# Tariq.net
KiCad netlist of a schematic drawn in EAGLE
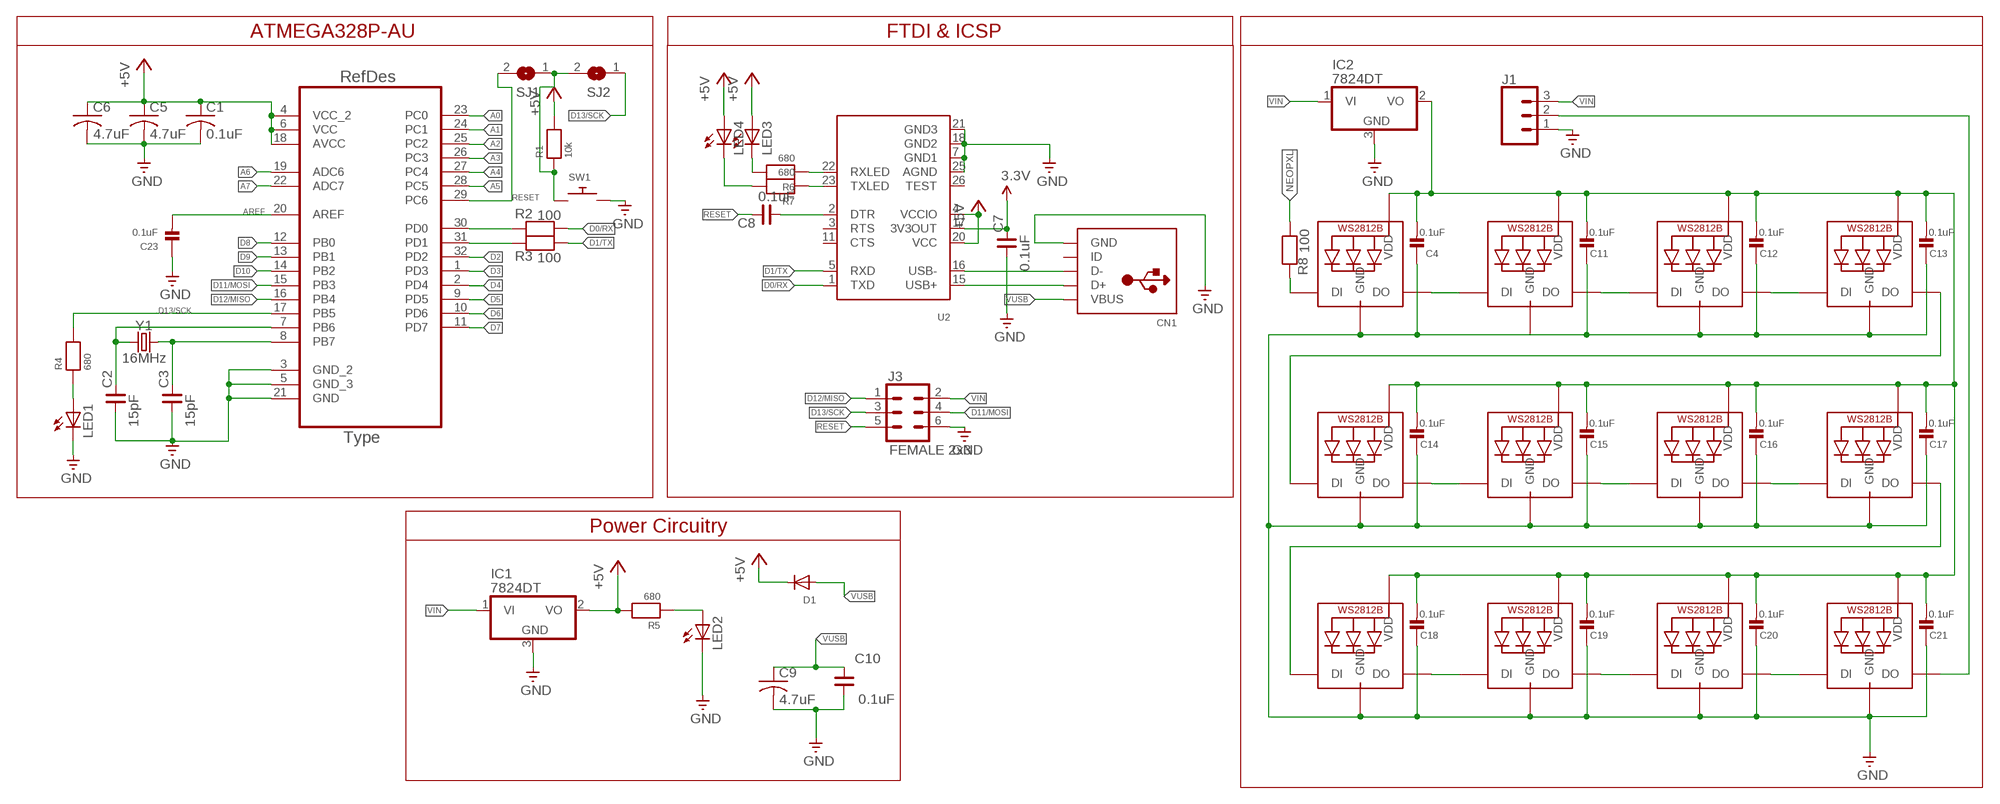
[diagram p0: schematic, sheet 1]

(export (version "E")
  (design (tool "Eeschema 10.0.6"))
  (components
    (comp (ref "C1")
      (value "0.1uF")
      (footprint "eagle-import:C0805")
      (libsource (lib "eagle-import") (part "C-USC0805"))
    )
    (comp (ref "C2")
      (value "15pF")
      (footprint "eagle-import:0805")
      (libsource (lib "eagle-import") (part "CNP-0805"))
    )
    (comp (ref "C3")
      (value "15pF")
      (footprint "eagle-import:0805")
      (libsource (lib "eagle-import") (part "CNP-0805"))
    )
    (comp (ref "C4")
      (value "0.1uF")
      (footprint "eagle-import:0603")
      (libsource (lib "eagle-import") (part "CAP_CERAMIC0603"))
    )
    (comp (ref "C5")
      (value "4.7uF")
      (footprint "eagle-import:C0805")
      (libsource (lib "eagle-import") (part "C-USC0805"))
    )
    (comp (ref "C6")
      (value "4.7uF")
      (footprint "eagle-import:C0805")
      (libsource (lib "eagle-import") (part "C-USC0805"))
    )
    (comp (ref "C7")
      (value "0.1uF")
      (footprint "eagle-import:0805")
      (libsource (lib "eagle-import") (part "CNP-0805"))
    )
    (comp (ref "C8")
      (value "0.1uF")
      (footprint "eagle-import:0805")
      (libsource (lib "eagle-import") (part "CNP-0805"))
    )
    (comp (ref "C9")
      (value "4.7uF")
      (footprint "eagle-import:C0805")
      (libsource (lib "eagle-import") (part "C-USC0805"))
    )
    (comp (ref "C10")
      (value "0.1uF")
      (footprint "eagle-import:0805")
      (libsource (lib "eagle-import") (part "CNP-0805"))
    )
    (comp (ref "C11")
      (value "0.1uF")
      (footprint "eagle-import:0603")
      (libsource (lib "eagle-import") (part "CAP_CERAMIC0603"))
    )
    (comp (ref "C12")
      (value "0.1uF")
      (footprint "eagle-import:0603")
      (libsource (lib "eagle-import") (part "CAP_CERAMIC0603"))
    )
    (comp (ref "C13")
      (value "0.1uF")
      (footprint "eagle-import:0603")
      (libsource (lib "eagle-import") (part "CAP_CERAMIC0603"))
    )
    (comp (ref "C14")
      (value "0.1uF")
      (footprint "eagle-import:0603")
      (libsource (lib "eagle-import") (part "CAP_CERAMIC0603"))
    )
    (comp (ref "C15")
      (value "0.1uF")
      (footprint "eagle-import:0603")
      (libsource (lib "eagle-import") (part "CAP_CERAMIC0603"))
    )
    (comp (ref "C16")
      (value "0.1uF")
      (footprint "eagle-import:0603")
      (libsource (lib "eagle-import") (part "CAP_CERAMIC0603"))
    )
    (comp (ref "C17")
      (value "0.1uF")
      (footprint "eagle-import:0603")
      (libsource (lib "eagle-import") (part "CAP_CERAMIC0603"))
    )
    (comp (ref "C18")
      (value "0.1uF")
      (footprint "eagle-import:0603")
      (libsource (lib "eagle-import") (part "CAP_CERAMIC0603"))
    )
    (comp (ref "C19")
      (value "0.1uF")
      (footprint "eagle-import:0603")
      (libsource (lib "eagle-import") (part "CAP_CERAMIC0603"))
    )
    (comp (ref "C20")
      (value "0.1uF")
      (footprint "eagle-import:0603")
      (libsource (lib "eagle-import") (part "CAP_CERAMIC0603"))
    )
    (comp (ref "C21")
      (value "0.1uF")
      (footprint "eagle-import:0603")
      (libsource (lib "eagle-import") (part "CAP_CERAMIC0603"))
    )
    (comp (ref "C23")
      (value "0.1uF")
      (footprint "eagle-import:0603")
      (libsource (lib "eagle-import") (part "CAP_CERAMIC0603"))
    )
    (comp (ref "CN1")
      (value "USBMINIB")
      (footprint "eagle-import:USB-MINIB")
      (libsource (lib "eagle-import") (part "USBMINIB"))
    )
    (comp (ref "D1")
      (value "DIODESOD-123")
      (footprint "eagle-import:SOD-123")
      (libsource (lib "eagle-import") (part "DIODESOD-123"))
    )
    (comp (ref "IC1")
      (value "7824DT")
      (footprint "eagle-import:TO252")
      (libsource (lib "eagle-import") (part "78DT24"))
    )
    (comp (ref "IC2")
      (value "7824DT")
      (footprint "eagle-import:TO252")
      (libsource (lib "eagle-import") (part "78DT24"))
    )
    (comp (ref "J1")
      (value "CONN_03")
      (footprint "eagle-import:1X03")
      (libsource (lib "eagle-import") (part "CONN_03"))
    )
    (comp (ref "J3")
      (value "FEMALE 2x3")
      (footprint "eagle-import:2X3")
      (libsource (lib "eagle-import") (part "CONN_03X2FEMALE"))
    )
    (comp (ref "LED1")
      (value "LEDCHIPLED_0805")
      (footprint "eagle-import:CHIPLED_0805")
      (libsource (lib "eagle-import") (part "LEDCHIPLED_0805"))
    )
    (comp (ref "LED2")
      (value "LEDCHIPLED_0805")
      (footprint "eagle-import:CHIPLED_0805")
      (libsource (lib "eagle-import") (part "LEDCHIPLED_0805"))
    )
    (comp (ref "LED3")
      (value "LEDCHIPLED_0805")
      (footprint "eagle-import:CHIPLED_0805")
      (libsource (lib "eagle-import") (part "LEDCHIPLED_0805"))
    )
    (comp (ref "LED4")
      (value "LEDCHIPLED_0805")
      (footprint "eagle-import:CHIPLED_0805")
      (libsource (lib "eagle-import") (part "LEDCHIPLED_0805"))
    )
    (comp (ref "LED5")
      (value "WS2812B5050")
      (footprint "eagle-import:WS2812B")
      (libsource (lib "eagle-import") (part "WS2812B5050"))
    )
    (comp (ref "LED6")
      (value "WS2812B5050")
      (footprint "eagle-import:WS2812B")
      (libsource (lib "eagle-import") (part "WS2812B5050"))
    )
    (comp (ref "LED7")
      (value "WS2812B5050")
      (footprint "eagle-import:WS2812B")
      (libsource (lib "eagle-import") (part "WS2812B5050"))
    )
    (comp (ref "LED8")
      (value "WS2812B5050")
      (footprint "eagle-import:WS2812B")
      (libsource (lib "eagle-import") (part "WS2812B5050"))
    )
    (comp (ref "LED9")
      (value "WS2812B5050")
      (footprint "eagle-import:WS2812B")
      (libsource (lib "eagle-import") (part "WS2812B5050"))
    )
    (comp (ref "LED10")
      (value "WS2812B5050")
      (footprint "eagle-import:WS2812B")
      (libsource (lib "eagle-import") (part "WS2812B5050"))
    )
    (comp (ref "LED11")
      (value "WS2812B5050")
      (footprint "eagle-import:WS2812B")
      (libsource (lib "eagle-import") (part "WS2812B5050"))
    )
    (comp (ref "LED12")
      (value "WS2812B5050")
      (footprint "eagle-import:WS2812B")
      (libsource (lib "eagle-import") (part "WS2812B5050"))
    )
    (comp (ref "LED13")
      (value "WS2812B5050")
      (footprint "eagle-import:WS2812B")
      (libsource (lib "eagle-import") (part "WS2812B5050"))
    )
    (comp (ref "LED14")
      (value "WS2812B5050")
      (footprint "eagle-import:WS2812B")
      (libsource (lib "eagle-import") (part "WS2812B5050"))
    )
    (comp (ref "LED15")
      (value "WS2812B5050")
      (footprint "eagle-import:WS2812B")
      (libsource (lib "eagle-import") (part "WS2812B5050"))
    )
    (comp (ref "LED16")
      (value "WS2812B5050")
      (footprint "eagle-import:WS2812B")
      (libsource (lib "eagle-import") (part "WS2812B5050"))
    )
    (comp (ref "R1")
      (value "10k")
      (footprint "eagle-import:0603")
      (libsource (lib "eagle-import") (part "RESISTOR0603"))
    )
    (comp (ref "R2")
      (value "100")
      (footprint "eagle-import:0603")
      (libsource (lib "eagle-import") (part "RESISTOR0603"))
    )
    (comp (ref "R3")
      (value "100")
      (footprint "eagle-import:0603")
      (libsource (lib "eagle-import") (part "RESISTOR0603"))
    )
    (comp (ref "R4")
      (value "680")
      (footprint "eagle-import:0603")
      (libsource (lib "eagle-import") (part "RESISTOR0603"))
    )
    (comp (ref "R5")
      (value "680")
      (footprint "eagle-import:0603")
      (libsource (lib "eagle-import") (part "RESISTOR0603"))
    )
    (comp (ref "R6")
      (value "680")
      (footprint "eagle-import:0603")
      (libsource (lib "eagle-import") (part "RESISTOR0603"))
    )
    (comp (ref "R7")
      (value "680")
      (footprint "eagle-import:0603")
      (libsource (lib "eagle-import") (part "RESISTOR0603"))
    )
    (comp (ref "R8")
      (value "100")
      (footprint "eagle-import:0603")
      (libsource (lib "eagle-import") (part "RESISTOR0603"))
    )
    (comp (ref "SJ1")
      (value "SOLDERJUMPERWAVE")
      (footprint "eagle-import:SOLDERJUMPER_WAVE")
      (libsource (lib "eagle-import") (part "SOLDERJUMPERWAVE"))
    )
    (comp (ref "SJ2")
      (value "SOLDERJUMPERWAVE")
      (footprint "eagle-import:SOLDERJUMPER_WAVE")
      (libsource (lib "eagle-import") (part "SOLDERJUMPERWAVE"))
    )
    (comp (ref "SW1")
      (value "SWITCH_PUSHBUTTONEVQ-PE")
      (footprint "eagle-import:TACT_PANA-EVQ")
      (libsource (lib "eagle-import") (part "SWITCH_PUSHBUTTONEVQ-PE"))
    )
    (comp (ref "U1")
      (value "ATMEGA328P-AU")
      (footprint "eagle-import:QFP80P900X900X120-32N")
      (libsource (lib "eagle-import") (part "ATMEGA328P-AU"))
    )
    (comp (ref "U2")
      (value "FT232RLSSOP28")
      (footprint "eagle-import:SSOP28DB")
      (libsource (lib "eagle-import") (part "FT232RLSSOP28"))
    )
    (comp (ref "Y1")
      (value "16MHz")
      (footprint "eagle-import:HC49US")
      (libsource (lib "eagle-import") (part "CRYSTAL-16MHZPTH-HC49US"))
    )
  )
  (nets
    (net (code "1") (name "+5V") (class "Default")
      (node (ref "C1") (pin "1") (pinfunction "1_1") (pintype "passive"))
      (node (ref "C5") (pin "1") (pinfunction "1_1") (pintype "passive"))
      (node (ref "C6") (pin "1") (pinfunction "1_1") (pintype "passive"))
      (node (ref "D1") (pin "C") (pinfunction "C_C") (pintype "passive"))
      (node (ref "IC1") (pin "2") (pinfunction "VO_2") (pintype "passive"))
      (node (ref "LED3") (pin "A") (pinfunction "A_A") (pintype "passive"))
      (node (ref "LED4") (pin "A") (pinfunction "A_A") (pintype "passive"))
      (node (ref "R1") (pin "2") (pinfunction "2_2") (pintype "passive"))
      (node (ref "R5") (pin "2") (pinfunction "2_2") (pintype "passive"))
      (node (ref "U1") (pin "18") (pinfunction "AVCC_18") (pintype "power_in"))
      (node (ref "U1") (pin "4") (pinfunction "VCC_2_4") (pintype "power_in"))
      (node (ref "U1") (pin "6") (pinfunction "VCC_6") (pintype "power_in"))
      (node (ref "U2") (pin "20") (pinfunction "VCC_20") (pintype "power_in"))
      (node (ref "U2") (pin "4") (pinfunction "VCCIO_4") (pintype "power_in"))
    )
    (net (code "2") (name "/AREF") (class "Default")
      (node (ref "C23") (pin "2") (pinfunction "P$2_2") (pintype "passive"))
      (node (ref "U1") (pin "20") (pinfunction "AREF_20") (pintype "input"))
    )
    (net (code "3") (name "3.3V") (class "Default")
      (node (ref "C7") (pin "2") (pinfunction "2_2") (pintype "passive"))
      (node (ref "U2") (pin "17") (pinfunction "3V3OUT_17") (pintype "power_in"))
    )
    (net (code "4") (name "A0") (class "Default")
      (node (ref "U1") (pin "23") (pinfunction "PC0_23") (pintype "bidirectional"))
    )
    (net (code "5") (name "A1") (class "Default")
      (node (ref "U1") (pin "24") (pinfunction "PC1_24") (pintype "bidirectional"))
    )
    (net (code "6") (name "A2") (class "Default")
      (node (ref "U1") (pin "25") (pinfunction "PC2_25") (pintype "bidirectional"))
    )
    (net (code "7") (name "A3") (class "Default")
      (node (ref "U1") (pin "26") (pinfunction "PC3_26") (pintype "bidirectional"))
    )
    (net (code "8") (name "A4") (class "Default")
      (node (ref "U1") (pin "27") (pinfunction "PC4_27") (pintype "bidirectional"))
    )
    (net (code "9") (name "A5") (class "Default")
      (node (ref "U1") (pin "28") (pinfunction "PC5_28") (pintype "bidirectional"))
    )
    (net (code "10") (name "A6") (class "Default")
      (node (ref "U1") (pin "19") (pinfunction "ADC6_19") (pintype "input"))
    )
    (net (code "11") (name "A7") (class "Default")
      (node (ref "U1") (pin "22") (pinfunction "ADC7_22") (pintype "input"))
    )
    (net (code "12") (name "D0{slash}RX") (class "Default")
      (node (ref "R2") (pin "1") (pinfunction "1_1") (pintype "passive"))
      (node (ref "U2") (pin "1") (pinfunction "TXD_1") (pintype "output"))
    )
    (net (code "13") (name "D1{slash}TX") (class "Default")
      (node (ref "R3") (pin "1") (pinfunction "1_1") (pintype "passive"))
      (node (ref "U2") (pin "5") (pinfunction "RXD_5") (pintype "input"))
    )
    (net (code "14") (name "D2") (class "Default")
      (node (ref "U1") (pin "32") (pinfunction "PD2_32") (pintype "bidirectional"))
    )
    (net (code "15") (name "D3") (class "Default")
      (node (ref "U1") (pin "1") (pinfunction "PD3_1") (pintype "bidirectional"))
    )
    (net (code "16") (name "D4") (class "Default")
      (node (ref "U1") (pin "2") (pinfunction "PD4_2") (pintype "bidirectional"))
    )
    (net (code "17") (name "D5") (class "Default")
      (node (ref "U1") (pin "9") (pinfunction "PD5_9") (pintype "bidirectional"))
    )
    (net (code "18") (name "D6") (class "Default")
      (node (ref "U1") (pin "10") (pinfunction "PD6_10") (pintype "bidirectional"))
    )
    (net (code "19") (name "D7") (class "Default")
      (node (ref "U1") (pin "11") (pinfunction "PD7_11") (pintype "bidirectional"))
    )
    (net (code "20") (name "D8") (class "Default")
      (node (ref "U1") (pin "12") (pinfunction "PB0_12") (pintype "bidirectional"))
    )
    (net (code "21") (name "D9") (class "Default")
      (node (ref "U1") (pin "13") (pinfunction "PB1_13") (pintype "bidirectional"))
    )
    (net (code "22") (name "D10") (class "Default")
      (node (ref "U1") (pin "14") (pinfunction "PB2_14") (pintype "bidirectional"))
    )
    (net (code "23") (name "D11{slash}MOSI") (class "Default")
      (node (ref "J3") (pin "4") (pinfunction "4_4") (pintype "bidirectional"))
      (node (ref "U1") (pin "15") (pinfunction "PB3_15") (pintype "bidirectional"))
    )
    (net (code "24") (name "D12{slash}MISO") (class "Default")
      (node (ref "J3") (pin "1") (pinfunction "1_1") (pintype "bidirectional"))
      (node (ref "U1") (pin "16") (pinfunction "PB4_16") (pintype "bidirectional"))
    )
    (net (code "25") (name "D13{slash}SCK") (class "Default")
      (node (ref "J3") (pin "3") (pinfunction "3_3") (pintype "bidirectional"))
      (node (ref "R4") (pin "2") (pinfunction "2_2") (pintype "passive"))
      (node (ref "SJ2") (pin "1") (pinfunction "1_1") (pintype "passive"))
      (node (ref "U1") (pin "17") (pinfunction "PB5_17") (pintype "bidirectional"))
    )
    (net (code "26") (name "GND") (class "Default")
      (node (ref "C1") (pin "2") (pinfunction "2_2") (pintype "passive"))
      (node (ref "C10") (pin "1") (pinfunction "1_1") (pintype "passive"))
      (node (ref "C11") (pin "1") (pinfunction "P$1_1") (pintype "passive"))
      (node (ref "C12") (pin "1") (pinfunction "P$1_1") (pintype "passive"))
      (node (ref "C13") (pin "1") (pinfunction "P$1_1") (pintype "passive"))
      (node (ref "C14") (pin "1") (pinfunction "P$1_1") (pintype "passive"))
      (node (ref "C15") (pin "1") (pinfunction "P$1_1") (pintype "passive"))
      (node (ref "C16") (pin "1") (pinfunction "P$1_1") (pintype "passive"))
      (node (ref "C17") (pin "1") (pinfunction "P$1_1") (pintype "passive"))
      (node (ref "C18") (pin "1") (pinfunction "P$1_1") (pintype "passive"))
      (node (ref "C19") (pin "1") (pinfunction "P$1_1") (pintype "passive"))
      (node (ref "C2") (pin "1") (pinfunction "1_1") (pintype "passive"))
      (node (ref "C20") (pin "1") (pinfunction "P$1_1") (pintype "passive"))
      (node (ref "C21") (pin "1") (pinfunction "P$1_1") (pintype "passive"))
      (node (ref "C23") (pin "1") (pinfunction "P$1_1") (pintype "passive"))
      (node (ref "C3") (pin "1") (pinfunction "1_1") (pintype "passive"))
      (node (ref "C4") (pin "1") (pinfunction "P$1_1") (pintype "passive"))
      (node (ref "C5") (pin "2") (pinfunction "2_2") (pintype "passive"))
      (node (ref "C6") (pin "2") (pinfunction "2_2") (pintype "passive"))
      (node (ref "C7") (pin "1") (pinfunction "1_1") (pintype "passive"))
      (node (ref "C9") (pin "2") (pinfunction "2_2") (pintype "passive"))
      (node (ref "CN1") (pin "GND") (pinfunction "GND_GND") (pintype "power_in"))
      (node (ref "IC1") (pin "3") (pinfunction "GND_3") (pintype "passive"))
      (node (ref "IC2") (pin "3") (pinfunction "GND_3") (pintype "passive"))
      (node (ref "J1") (pin "1") (pinfunction "1_1") (pintype "passive"))
      (node (ref "J3") (pin "6") (pinfunction "6_6") (pintype "bidirectional"))
      (node (ref "LED1") (pin "C") (pinfunction "C_C") (pintype "passive"))
      (node (ref "LED10") (pin "3-GND") (pinfunction "GND_3-GND") (pintype "power_in"))
      (node (ref "LED11") (pin "3-GND") (pinfunction "GND_3-GND") (pintype "power_in"))
      (node (ref "LED12") (pin "3-GND") (pinfunction "GND_3-GND") (pintype "power_in"))
      (node (ref "LED13") (pin "3-GND") (pinfunction "GND_3-GND") (pintype "power_in"))
      (node (ref "LED14") (pin "3-GND") (pinfunction "GND_3-GND") (pintype "power_in"))
      (node (ref "LED15") (pin "3-GND") (pinfunction "GND_3-GND") (pintype "power_in"))
      (node (ref "LED16") (pin "3-GND") (pinfunction "GND_3-GND") (pintype "power_in"))
      (node (ref "LED2") (pin "C") (pinfunction "C_C") (pintype "passive"))
      (node (ref "LED5") (pin "3-GND") (pinfunction "GND_3-GND") (pintype "power_in"))
      (node (ref "LED6") (pin "3-GND") (pinfunction "GND_3-GND") (pintype "power_in"))
      (node (ref "LED7") (pin "3-GND") (pinfunction "GND_3-GND") (pintype "power_in"))
      (node (ref "LED8") (pin "3-GND") (pinfunction "GND_3-GND") (pintype "power_in"))
      (node (ref "LED9") (pin "3-GND") (pinfunction "GND_3-GND") (pintype "power_in"))
      (node (ref "SW1") (pin "P$2") (pinfunction "P$2_P$2") (pintype "passive"))
      (node (ref "U1") (pin "21") (pinfunction "GND_21") (pintype "passive"))
      (node (ref "U1") (pin "3") (pinfunction "GND_2_3") (pintype "passive"))
      (node (ref "U1") (pin "5") (pinfunction "GND_3_5") (pintype "passive"))
      (node (ref "U2") (pin "18") (pinfunction "GND2_18") (pintype "power_in"))
      (node (ref "U2") (pin "21") (pinfunction "GND3_21") (pintype "power_in"))
      (node (ref "U2") (pin "25") (pinfunction "AGND_25") (pintype "power_in"))
      (node (ref "U2") (pin "7") (pinfunction "GND1_7") (pintype "power_in"))
    )
    (net (code "27") (name "NEOPXL") (class "Default")
      (node (ref "R8") (pin "1") (pinfunction "1_1") (pintype "passive"))
    )
    (net (code "28") (name "Net-(C11-P$2)") (class "Default")
      (node (ref "C11") (pin "2") (pinfunction "P$2_2") (pintype "passive"))
      (node (ref "C12") (pin "2") (pinfunction "P$2_2") (pintype "passive"))
      (node (ref "C13") (pin "2") (pinfunction "P$2_2") (pintype "passive"))
      (node (ref "C14") (pin "2") (pinfunction "P$2_2") (pintype "passive"))
      (node (ref "C15") (pin "2") (pinfunction "P$2_2") (pintype "passive"))
      (node (ref "C16") (pin "2") (pinfunction "P$2_2") (pintype "passive"))
      (node (ref "C17") (pin "2") (pinfunction "P$2_2") (pintype "passive"))
      (node (ref "C18") (pin "2") (pinfunction "P$2_2") (pintype "passive"))
      (node (ref "C19") (pin "2") (pinfunction "P$2_2") (pintype "passive"))
      (node (ref "C20") (pin "2") (pinfunction "P$2_2") (pintype "passive"))
      (node (ref "C21") (pin "2") (pinfunction "P$2_2") (pintype "passive"))
      (node (ref "C4") (pin "2") (pinfunction "P$2_2") (pintype "passive"))
      (node (ref "IC2") (pin "2") (pinfunction "VO_2") (pintype "passive"))
      (node (ref "LED10") (pin "1-VDD") (pinfunction "VDD_1-VDD") (pintype "power_in"))
      (node (ref "LED11") (pin "1-VDD") (pinfunction "VDD_1-VDD") (pintype "power_in"))
      (node (ref "LED12") (pin "1-VDD") (pinfunction "VDD_1-VDD") (pintype "power_in"))
      (node (ref "LED13") (pin "1-VDD") (pinfunction "VDD_1-VDD") (pintype "power_in"))
      (node (ref "LED14") (pin "1-VDD") (pinfunction "VDD_1-VDD") (pintype "power_in"))
      (node (ref "LED15") (pin "1-VDD") (pinfunction "VDD_1-VDD") (pintype "power_in"))
      (node (ref "LED16") (pin "1-VDD") (pinfunction "VDD_1-VDD") (pintype "power_in"))
      (node (ref "LED5") (pin "1-VDD") (pinfunction "VDD_1-VDD") (pintype "power_in"))
      (node (ref "LED6") (pin "1-VDD") (pinfunction "VDD_1-VDD") (pintype "power_in"))
      (node (ref "LED7") (pin "1-VDD") (pinfunction "VDD_1-VDD") (pintype "power_in"))
      (node (ref "LED8") (pin "1-VDD") (pinfunction "VDD_1-VDD") (pintype "power_in"))
      (node (ref "LED9") (pin "1-VDD") (pinfunction "VDD_1-VDD") (pintype "power_in"))
    )
    (net (code "29") (name "Net-(LED1-PadA)") (class "Default")
      (node (ref "LED1") (pin "A") (pinfunction "A_A") (pintype "passive"))
      (node (ref "R4") (pin "1") (pinfunction "1_1") (pintype "passive"))
    )
    (net (code "30") (name "Net-(LED2-PadA)") (class "Default")
      (node (ref "LED2") (pin "A") (pinfunction "A_A") (pintype "passive"))
      (node (ref "R5") (pin "1") (pinfunction "1_1") (pintype "passive"))
    )
    (net (code "31") (name "Net-(LED3-PadC)") (class "Default")
      (node (ref "LED3") (pin "C") (pinfunction "C_C") (pintype "passive"))
      (node (ref "R6") (pin "2") (pinfunction "2_2") (pintype "passive"))
    )
    (net (code "32") (name "Net-(LED4-PadC)") (class "Default")
      (node (ref "LED4") (pin "C") (pinfunction "C_C") (pintype "passive"))
      (node (ref "R7") (pin "2") (pinfunction "2_2") (pintype "passive"))
    )
    (net (code "33") (name "Net-(LED5-DI)") (class "Default")
      (node (ref "LED5") (pin "4-DIN") (pinfunction "DI_4-DIN") (pintype "input"))
      (node (ref "R8") (pin "2") (pinfunction "2_2") (pintype "passive"))
    )
    (net (code "34") (name "Net-(LED5-DO)") (class "Default")
      (node (ref "LED5") (pin "2-DOUT") (pinfunction "DO_2-DOUT") (pintype "output"))
      (node (ref "LED6") (pin "4-DIN") (pinfunction "DI_4-DIN") (pintype "input"))
    )
    (net (code "35") (name "Net-(LED6-DO)") (class "Default")
      (node (ref "LED6") (pin "2-DOUT") (pinfunction "DO_2-DOUT") (pintype "output"))
      (node (ref "LED7") (pin "4-DIN") (pinfunction "DI_4-DIN") (pintype "input"))
    )
    (net (code "36") (name "Net-(LED7-DO)") (class "Default")
      (node (ref "LED7") (pin "2-DOUT") (pinfunction "DO_2-DOUT") (pintype "output"))
      (node (ref "LED8") (pin "4-DIN") (pinfunction "DI_4-DIN") (pintype "input"))
    )
    (net (code "37") (name "Net-(LED8-DO)") (class "Default")
      (node (ref "LED8") (pin "2-DOUT") (pinfunction "DO_2-DOUT") (pintype "output"))
      (node (ref "LED9") (pin "4-DIN") (pinfunction "DI_4-DIN") (pintype "input"))
    )
    (net (code "38") (name "Net-(LED10-DI)") (class "Default")
      (node (ref "LED10") (pin "4-DIN") (pinfunction "DI_4-DIN") (pintype "input"))
      (node (ref "LED9") (pin "2-DOUT") (pinfunction "DO_2-DOUT") (pintype "output"))
    )
    (net (code "39") (name "Net-(LED10-DO)") (class "Default")
      (node (ref "LED10") (pin "2-DOUT") (pinfunction "DO_2-DOUT") (pintype "output"))
      (node (ref "LED11") (pin "4-DIN") (pinfunction "DI_4-DIN") (pintype "input"))
    )
    (net (code "40") (name "Net-(LED11-DO)") (class "Default")
      (node (ref "LED11") (pin "2-DOUT") (pinfunction "DO_2-DOUT") (pintype "output"))
      (node (ref "LED12") (pin "4-DIN") (pinfunction "DI_4-DIN") (pintype "input"))
    )
    (net (code "41") (name "Net-(LED12-DO)") (class "Default")
      (node (ref "LED12") (pin "2-DOUT") (pinfunction "DO_2-DOUT") (pintype "output"))
      (node (ref "LED13") (pin "4-DIN") (pinfunction "DI_4-DIN") (pintype "input"))
    )
    (net (code "42") (name "Net-(LED13-DO)") (class "Default")
      (node (ref "LED13") (pin "2-DOUT") (pinfunction "DO_2-DOUT") (pintype "output"))
      (node (ref "LED14") (pin "4-DIN") (pinfunction "DI_4-DIN") (pintype "input"))
    )
    (net (code "43") (name "Net-(LED14-DO)") (class "Default")
      (node (ref "LED14") (pin "2-DOUT") (pinfunction "DO_2-DOUT") (pintype "output"))
      (node (ref "LED15") (pin "4-DIN") (pinfunction "DI_4-DIN") (pintype "input"))
    )
    (net (code "44") (name "Net-(LED15-DO)") (class "Default")
      (node (ref "LED15") (pin "2-DOUT") (pinfunction "DO_2-DOUT") (pintype "output"))
      (node (ref "LED16") (pin "4-DIN") (pinfunction "DI_4-DIN") (pintype "input"))
    )
    (net (code "45") (name "Net-(LED16-DO)") (class "Default")
      (node (ref "J1") (pin "2") (pinfunction "2_2") (pintype "passive"))
      (node (ref "LED16") (pin "2-DOUT") (pinfunction "DO_2-DOUT") (pintype "output"))
    )
    (net (code "46") (name "Net-(R1-Pad1)") (class "Default")
      (node (ref "R1") (pin "1") (pinfunction "1_1") (pintype "passive"))
      (node (ref "SJ1") (pin "1") (pinfunction "1_1") (pintype "passive"))
      (node (ref "SJ2") (pin "2") (pinfunction "2_2") (pintype "passive"))
      (node (ref "SW1") (pin "P$1") (pinfunction "P$1_P$1") (pintype "passive"))
    )
    (net (code "47") (name "Net-(U1-PB6)") (class "Default")
      (node (ref "C2") (pin "2") (pinfunction "2_2") (pintype "passive"))
      (node (ref "U1") (pin "7") (pinfunction "PB6_7") (pintype "bidirectional"))
      (node (ref "Y1") (pin "1") (pinfunction "1_1") (pintype "passive"))
    )
    (net (code "48") (name "Net-(U1-PB7)") (class "Default")
      (node (ref "C3") (pin "2") (pinfunction "2_2") (pintype "passive"))
      (node (ref "U1") (pin "8") (pinfunction "PB7_8") (pintype "bidirectional"))
      (node (ref "Y1") (pin "2") (pinfunction "2_2") (pintype "passive"))
    )
    (net (code "49") (name "Net-(U1-PD0)") (class "Default")
      (node (ref "R2") (pin "2") (pinfunction "2_2") (pintype "passive"))
      (node (ref "U1") (pin "30") (pinfunction "PD0_30") (pintype "bidirectional"))
    )
    (net (code "50") (name "Net-(U1-PD1)") (class "Default")
      (node (ref "R3") (pin "2") (pinfunction "2_2") (pintype "passive"))
      (node (ref "U1") (pin "31") (pinfunction "PD1_31") (pintype "bidirectional"))
    )
    (net (code "51") (name "Net-(U2-DTR)") (class "Default")
      (node (ref "C8") (pin "1") (pinfunction "1_1") (pintype "passive"))
      (node (ref "U2") (pin "2") (pinfunction "DTR_2") (pintype "bidirectional"))
    )
    (net (code "52") (name "Net-(U2-RXLED)") (class "Default")
      (node (ref "R6") (pin "1") (pinfunction "1_1") (pintype "passive"))
      (node (ref "U2") (pin "22") (pinfunction "RXLED_22") (pintype "bidirectional"))
    )
    (net (code "53") (name "Net-(U2-TXLED)") (class "Default")
      (node (ref "R7") (pin "1") (pinfunction "1_1") (pintype "passive"))
      (node (ref "U2") (pin "23") (pinfunction "TXLED_23") (pintype "bidirectional"))
    )
    (net (code "54") (name "Net-(U2-USB+)") (class "Default")
      (node (ref "CN1") (pin "D+") (pinfunction "D+_D+") (pintype "bidirectional"))
      (node (ref "U2") (pin "15") (pinfunction "USB+_15") (pintype "bidirectional"))
    )
    (net (code "55") (name "Net-(U2-USB-)") (class "Default")
      (node (ref "CN1") (pin "D-") (pinfunction "D-_D-") (pintype "bidirectional"))
      (node (ref "U2") (pin "16") (pinfunction "USB-_16") (pintype "bidirectional"))
    )
    (net (code "56") (name "RESET") (class "Default")
      (node (ref "C8") (pin "2") (pinfunction "2_2") (pintype "passive"))
      (node (ref "J3") (pin "5") (pinfunction "5_5") (pintype "bidirectional"))
      (node (ref "SJ1") (pin "2") (pinfunction "2_2") (pintype "passive"))
      (node (ref "U1") (pin "29") (pinfunction "PC6_29") (pintype "bidirectional"))
    )
    (net (code "57") (name "VIN") (class "Default")
      (node (ref "IC1") (pin "1") (pinfunction "VI_1") (pintype "input"))
      (node (ref "IC2") (pin "1") (pinfunction "VI_1") (pintype "input"))
      (node (ref "J1") (pin "3") (pinfunction "3_3") (pintype "passive"))
      (node (ref "J3") (pin "2") (pinfunction "2_2") (pintype "bidirectional"))
    )
    (net (code "58") (name "VUSB") (class "Default")
      (node (ref "C10") (pin "2") (pinfunction "2_2") (pintype "passive"))
      (node (ref "C9") (pin "1") (pinfunction "1_1") (pintype "passive"))
      (node (ref "CN1") (pin "VBUS") (pinfunction "VBUS_VBUS") (pintype "power_in"))
      (node (ref "D1") (pin "A") (pinfunction "A_A") (pintype "passive"))
    )
    (net (code "59") (name "unconnected-(CN1-PadID)") (class "Default")
      (node (ref "CN1") (pin "ID") (pinfunction "ID_ID") (pintype "bidirectional"))
    )
    (net (code "60") (name "unconnected-(U2-CTS-Pad11)") (class "Default")
      (node (ref "U2") (pin "11") (pinfunction "CTS_11") (pintype "bidirectional"))
    )
    (net (code "61") (name "unconnected-(U2-RTS-Pad3)") (class "Default")
      (node (ref "U2") (pin "3") (pinfunction "RTS_3") (pintype "bidirectional"))
    )
    (net (code "62") (name "unconnected-(U2-TEST-Pad26)") (class "Default")
      (node (ref "U2") (pin "26") (pinfunction "TEST_26") (pintype "input"))
    )
  )
)
